# SmartThermo2_2.net
KiCad netlist of a schematic drawn in EAGLE
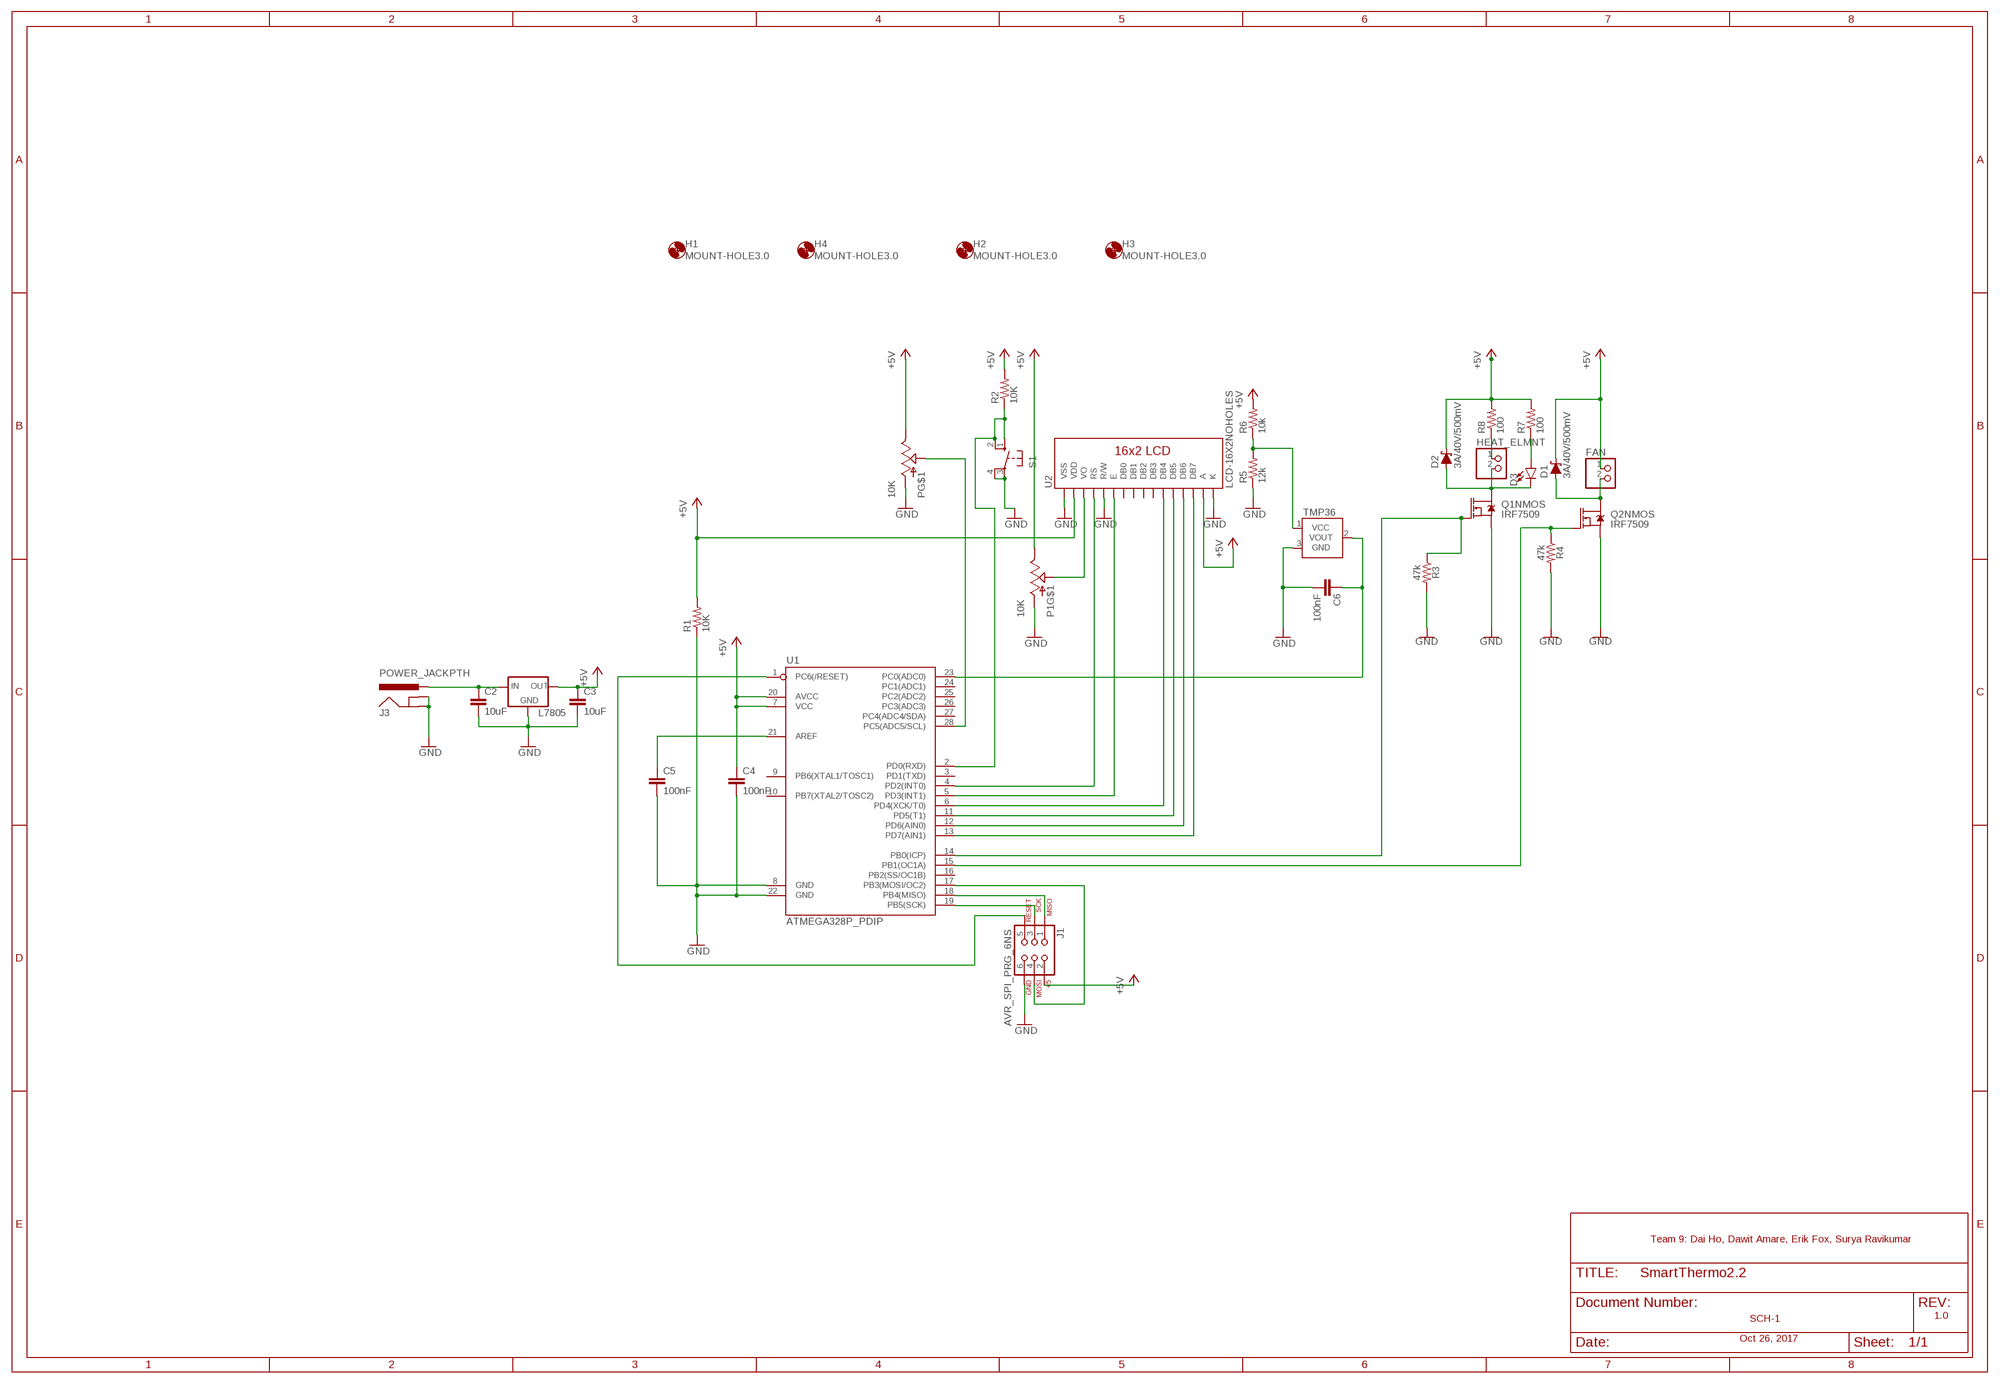
[diagram p0: schematic, sheet 1]

(export (version "E")
  (design (tool "Eeschema 10.0.6"))
  (components
    (comp (ref "C2")
      (value "10uF")
      (footprint "eagle-import:C7.5B3")
      (libsource (lib "eagle-import") (part "C7.5/3"))
    )
    (comp (ref "C3")
      (value "10uF")
      (footprint "eagle-import:C7.5B3")
      (libsource (lib "eagle-import") (part "C7.5/3"))
    )
    (comp (ref "C4")
      (value "100nF")
      (footprint "eagle-import:C2.5-2")
      (libsource (lib "eagle-import") (part "C2.5/2"))
    )
    (comp (ref "C5")
      (value "100nF")
      (footprint "eagle-import:C2.5-2")
      (libsource (lib "eagle-import") (part "C2.5/2"))
    )
    (comp (ref "C6")
      (value "100nF")
      (footprint "eagle-import:C2.5-2")
      (libsource (lib "eagle-import") (part "C2.5/2"))
    )
    (comp (ref "D1")
      (value "3A/40V/500mV")
      (footprint "eagle-import:SMA-DIODE")
      (libsource (lib "eagle-import") (part "DIODE-SCHOTTKY-B340A"))
    )
    (comp (ref "D2")
      (value "3A/40V/500mV")
      (footprint "eagle-import:SMA-DIODE")
      (libsource (lib "eagle-import") (part "DIODE-SCHOTTKY-B340A"))
    )
    (comp (ref "D3")
      (value "LED3MM")
      (footprint "eagle-import:LED_3MM")
      (libsource (lib "eagle-import") (part "LED3MM"))
    )
    (comp (ref "FAN")
      (value "PINHD-1X2/90")
      (footprint "eagle-import:1X02_90")
      (libsource (lib "eagle-import") (part "PINHD-1X2/90"))
    )
    (comp (ref "H1")
      (value "MOUNT-HOLE3.0")
      (footprint "eagle-import:3,0")
      (libsource (lib "eagle-import") (part "MOUNT-HOLE3.0"))
    )
    (comp (ref "H2")
      (value "MOUNT-HOLE3.0")
      (footprint "eagle-import:3,0")
      (libsource (lib "eagle-import") (part "MOUNT-HOLE3.0"))
    )
    (comp (ref "H3")
      (value "MOUNT-HOLE3.0")
      (footprint "eagle-import:3,0")
      (libsource (lib "eagle-import") (part "MOUNT-HOLE3.0"))
    )
    (comp (ref "H4")
      (value "MOUNT-HOLE3.0")
      (footprint "eagle-import:3,0")
      (libsource (lib "eagle-import") (part "MOUNT-HOLE3.0"))
    )
    (comp (ref "HEAT_ELMNT")
      (value "PINHD-1X2/90")
      (footprint "eagle-import:1X02_90")
      (libsource (lib "eagle-import") (part "PINHD-1X2/90"))
    )
    (comp (ref "J1")
      (value "AVR_SPI_PRG_6NS")
      (footprint "eagle-import:2X3-NS")
      (libsource (lib "eagle-import") (part "AVR_SPI_PRG_6NS"))
    )
    (comp (ref "J3")
      (value "POWER_JACKPTH")
      (footprint "eagle-import:POWER_JACK_PTH")
      (libsource (lib "eagle-import") (part "POWER_JACKPTH"))
    )
    (comp (ref "L7805")
      (value "78XXL")
      (footprint "eagle-import:78XXL")
      (libsource (lib "eagle-import") (part "78XXL"))
    )
    (comp (ref "P")
      (value "10K")
      (footprint "eagle-import:POT_PTH")
      (libsource (lib "eagle-import") (part "POT_SWITCHPOT_PTH"))
    )
    (comp (ref "P1")
      (value "10K")
      (footprint "eagle-import:POT_PTH")
      (libsource (lib "eagle-import") (part "POT_SWITCHPOT_PTH"))
    )
    (comp (ref "Q1")
      (value "IRF7509")
      (footprint "eagle-import:MSOP8")
      (libsource (lib "eagle-import") (part "IRF7509"))
    )
    (comp (ref "Q2")
      (value "IRF7509")
      (footprint "eagle-import:MSOP8")
      (libsource (lib "eagle-import") (part "IRF7509"))
    )
    (comp (ref "R1")
      (value "10K")
      (footprint "eagle-import:1206")
      (libsource (lib "eagle-import") (part "RESISTOR1206"))
    )
    (comp (ref "R2")
      (value "10K")
      (footprint "eagle-import:1206")
      (libsource (lib "eagle-import") (part "RESISTOR1206"))
    )
    (comp (ref "R3")
      (value "47k")
      (footprint "eagle-import:0603")
      (libsource (lib "eagle-import") (part "47KOHM-0603-1/10W-1%"))
    )
    (comp (ref "R4")
      (value "47k")
      (footprint "eagle-import:0603")
      (libsource (lib "eagle-import") (part "47KOHM-0603-1/10W-1%"))
    )
    (comp (ref "R5")
      (value "12k")
      (footprint "eagle-import:0204_5")
      (libsource (lib "eagle-import") (part "R-US_0204/5"))
    )
    (comp (ref "R6")
      (value "10k")
      (footprint "eagle-import:0204_5")
      (libsource (lib "eagle-import") (part "R-US_0204/5"))
    )
    (comp (ref "R7")
      (value "100")
      (footprint "eagle-import:0204_5")
      (libsource (lib "eagle-import") (part "R-US_0204/5"))
    )
    (comp (ref "R8")
      (value "100")
      (footprint "eagle-import:0204_5")
      (libsource (lib "eagle-import") (part "R-US_0204/5"))
    )
    (comp (ref "S1")
      (value "10-XX")
      (footprint "eagle-import:B3F-10XX")
      (fields (field (name "MPN") "B3F-1000"))
      (libsource (lib "eagle-import") (part "10-XX"))
    )
    (comp (ref "TMP36")
      (value "TMP36GT9")
      (footprint "eagle-import:TO-92")
      (libsource (lib "eagle-import") (part "TMP36GT9"))
    )
    (comp (ref "U1")
      (value "ATMEGA328P_PDIP")
      (footprint "eagle-import:DIL28-3")
      (libsource (lib "eagle-import") (part "ATMEGA328P_PDIP"))
    )
    (comp (ref "U2")
      (value "LCD-16X2NOHOLES")
      (footprint "eagle-import:LCD-16X2_NOHOLES")
      (libsource (lib "eagle-import") (part "LCD-16X2NOHOLES"))
    )
  )
  (nets
    (net (code "1") (name "+5V") (class "Default")
      (node (ref "C3") (pin "1") (pinfunction "1_1") (pintype "passive"))
      (node (ref "C4") (pin "1") (pinfunction "1_1") (pintype "passive"))
      (node (ref "D1") (pin "C") (pinfunction "C_C") (pintype "passive"))
      (node (ref "D2") (pin "C") (pinfunction "C_C") (pintype "passive"))
      (node (ref "FAN") (pin "1") (pinfunction "1_1") (pintype "passive"))
      (node (ref "J1") (pin "2") (pinfunction "2_2") (pintype "passive"))
      (node (ref "L7805") (pin "OUT") (pinfunction "OUT_OUT") (pintype "passive"))
      (node (ref "P") (pin "E@2") (pinfunction "E_E@2") (pintype "passive"))
      (node (ref "P1") (pin "E@2") (pinfunction "E_E@2") (pintype "passive"))
      (node (ref "R1") (pin "2") (pinfunction "2_2") (pintype "passive"))
      (node (ref "R2") (pin "2") (pinfunction "2_2") (pintype "passive"))
      (node (ref "R6") (pin "2") (pinfunction "2_2") (pintype "passive"))
      (node (ref "R7") (pin "2") (pinfunction "2_2") (pintype "passive"))
      (node (ref "R8") (pin "2") (pinfunction "2_2") (pintype "passive"))
      (node (ref "U1") (pin "20") (pinfunction "AVCC_20") (pintype "bidirectional"))
      (node (ref "U1") (pin "7") (pinfunction "VCC_7") (pintype "bidirectional"))
      (node (ref "U2") (pin "15") (pinfunction "A_15") (pintype "power_in"))
      (node (ref "U2") (pin "2") (pinfunction "VDD_2") (pintype "power_in"))
    )
    (net (code "2") (name "GND") (class "Default")
      (node (ref "C2") (pin "2") (pinfunction "2_2") (pintype "passive"))
      (node (ref "C3") (pin "2") (pinfunction "2_2") (pintype "passive"))
      (node (ref "C4") (pin "2") (pinfunction "2_2") (pintype "passive"))
      (node (ref "C5") (pin "2") (pinfunction "2_2") (pintype "passive"))
      (node (ref "C6") (pin "2") (pinfunction "2_2") (pintype "passive"))
      (node (ref "J1") (pin "6") (pinfunction "6_6") (pintype "passive"))
      (node (ref "J3") (pin "GND") (pinfunction "GND_GND") (pintype "bidirectional"))
      (node (ref "J3") (pin "GNDBREAK") (pinfunction "GNDBREAK_GNDBREAK") (pintype "bidirectional"))
      (node (ref "L7805") (pin "GND") (pinfunction "GND_GND") (pintype "input"))
      (node (ref "P") (pin "E@1") (pinfunction "A_E@1") (pintype "passive"))
      (node (ref "P1") (pin "E@1") (pinfunction "A_E@1") (pintype "passive"))
      (node (ref "Q1") (pin "1") (pinfunction "S_1") (pintype "bidirectional"))
      (node (ref "Q2") (pin "1") (pinfunction "S_1") (pintype "bidirectional"))
      (node (ref "R1") (pin "1") (pinfunction "1_1") (pintype "passive"))
      (node (ref "R3") (pin "2") (pinfunction "2_2") (pintype "passive"))
      (node (ref "R4") (pin "2") (pinfunction "2_2") (pintype "passive"))
      (node (ref "R5") (pin "1") (pinfunction "1_1") (pintype "passive"))
      (node (ref "S1") (pin "3") (pinfunction "P_3") (pintype "passive"))
      (node (ref "S1") (pin "4") (pinfunction "P1_4") (pintype "passive"))
      (node (ref "TMP36") (pin "3") (pinfunction "GND_3") (pintype "bidirectional"))
      (node (ref "U1") (pin "22") (pinfunction "GND_22") (pintype "bidirectional"))
      (node (ref "U1") (pin "8") (pinfunction "GND_8") (pintype "bidirectional"))
      (node (ref "U2") (pin "1") (pinfunction "VSS_1") (pintype "power_in"))
      (node (ref "U2") (pin "16") (pinfunction "K_16") (pintype "power_in"))
      (node (ref "U2") (pin "5") (pinfunction "R/W_5") (pintype "input"))
    )
    (net (code "3") (name "Net-(C2-Pad1)") (class "Default")
      (node (ref "C2") (pin "1") (pinfunction "1_1") (pintype "passive"))
      (node (ref "J3") (pin "PWR") (pinfunction "PWR_PWR") (pintype "bidirectional"))
      (node (ref "L7805") (pin "IN") (pinfunction "IN_IN") (pintype "input"))
    )
    (net (code "4") (name "Net-(D1-PadA)") (class "Default")
      (node (ref "D1") (pin "A") (pinfunction "A_A") (pintype "passive"))
      (node (ref "FAN") (pin "2") (pinfunction "2_2") (pintype "passive"))
      (node (ref "Q2") (pin "7") (pinfunction "D_7") (pintype "bidirectional"))
      (node (ref "Q2") (pin "8") (pinfunction "D_8") (pintype "bidirectional"))
    )
    (net (code "5") (name "Net-(D3-C)") (class "Default")
      (node (ref "D2") (pin "A") (pinfunction "A_A") (pintype "passive"))
      (node (ref "D3") (pin "K") (pinfunction "C_K") (pintype "passive"))
      (node (ref "HEAT_ELMNT") (pin "2") (pinfunction "2_2") (pintype "passive"))
      (node (ref "Q1") (pin "7") (pinfunction "D_7") (pintype "bidirectional"))
      (node (ref "Q1") (pin "8") (pinfunction "D_8") (pintype "bidirectional"))
    )
    (net (code "6") (name "Net-(D3-PadA)") (class "Default")
      (node (ref "D3") (pin "A") (pinfunction "A_A") (pintype "passive"))
      (node (ref "R7") (pin "1") (pinfunction "1_1") (pintype "passive"))
    )
    (net (code "7") (name "Net-(HEAT_ELMNT-Pad1)") (class "Default")
      (node (ref "HEAT_ELMNT") (pin "1") (pinfunction "1_1") (pintype "passive"))
      (node (ref "R8") (pin "1") (pinfunction "1_1") (pintype "passive"))
    )
    (net (code "8") (name "Net-(P1A-S)") (class "Default")
      (node (ref "P1") (pin "WAND") (pinfunction "S_WAND") (pintype "passive"))
      (node (ref "U2") (pin "3") (pinfunction "VO_3") (pintype "bidirectional"))
    )
    (net (code "9") (name "Net-(PA-S)") (class "Default")
      (node (ref "P") (pin "WAND") (pinfunction "S_WAND") (pintype "passive"))
      (node (ref "U1") (pin "28") (pinfunction "PC5(ADC5/SCL)_28") (pintype "bidirectional"))
    )
    (net (code "10") (name "Net-(Q1A-G)") (class "Default")
      (node (ref "Q1") (pin "2") (pinfunction "G_2") (pintype "bidirectional"))
      (node (ref "R3") (pin "1") (pinfunction "1_1") (pintype "passive"))
      (node (ref "U1") (pin "14") (pinfunction "PB0(ICP)_14") (pintype "bidirectional"))
    )
    (net (code "11") (name "Net-(Q2A-G)") (class "Default")
      (node (ref "Q2") (pin "2") (pinfunction "G_2") (pintype "bidirectional"))
      (node (ref "R4") (pin "1") (pinfunction "1_1") (pintype "passive"))
      (node (ref "U1") (pin "15") (pinfunction "PB1(OC1A)_15") (pintype "bidirectional"))
    )
    (net (code "12") (name "Net-(S1-S)") (class "Default")
      (node (ref "R2") (pin "1") (pinfunction "1_1") (pintype "passive"))
      (node (ref "S1") (pin "1") (pinfunction "S_1") (pintype "passive"))
      (node (ref "S1") (pin "2") (pinfunction "S1_2") (pintype "passive"))
      (node (ref "U1") (pin "2") (pinfunction "PD0(RXD)_2") (pintype "bidirectional"))
    )
    (net (code "13") (name "Net-(TMP36-VCC)") (class "Default")
      (node (ref "R5") (pin "2") (pinfunction "2_2") (pintype "passive"))
      (node (ref "R6") (pin "1") (pinfunction "1_1") (pintype "passive"))
      (node (ref "TMP36") (pin "1") (pinfunction "VCC_1") (pintype "bidirectional"))
    )
    (net (code "14") (name "Net-(TMP36-VOUT)") (class "Default")
      (node (ref "C6") (pin "1") (pinfunction "1_1") (pintype "passive"))
      (node (ref "TMP36") (pin "2") (pinfunction "VOUT_2") (pintype "bidirectional"))
      (node (ref "U1") (pin "23") (pinfunction "PC0(ADC0)_23") (pintype "bidirectional"))
    )
    (net (code "15") (name "Net-(U1-AREF)") (class "Default")
      (node (ref "C5") (pin "1") (pinfunction "1_1") (pintype "passive"))
      (node (ref "U1") (pin "21") (pinfunction "AREF_21") (pintype "bidirectional"))
    )
    (net (code "16") (name "Net-(U1-PB3(MOSI{slash}OC2))") (class "Default")
      (node (ref "J1") (pin "4") (pinfunction "4_4") (pintype "passive"))
      (node (ref "U1") (pin "17") (pinfunction "PB3(MOSI/OC2)_17") (pintype "bidirectional"))
    )
    (net (code "17") (name "Net-(U1-PB4(MISO))") (class "Default")
      (node (ref "J1") (pin "1") (pinfunction "1_1") (pintype "passive"))
      (node (ref "U1") (pin "18") (pinfunction "PB4(MISO)_18") (pintype "bidirectional"))
    )
    (net (code "18") (name "Net-(U1-PB5(SCK))") (class "Default")
      (node (ref "J1") (pin "3") (pinfunction "3_3") (pintype "passive"))
      (node (ref "U1") (pin "19") (pinfunction "PB5(SCK)_19") (pintype "bidirectional"))
    )
    (net (code "19") (name "Net-(U1-PC6({slash}RESET))") (class "Default")
      (node (ref "J1") (pin "5") (pinfunction "5_5") (pintype "passive"))
      (node (ref "U1") (pin "1") (pinfunction "PC6(/RESET)_1") (pintype "bidirectional"))
    )
    (net (code "20") (name "Net-(U1-PD2(INT0))") (class "Default")
      (node (ref "U1") (pin "4") (pinfunction "PD2(INT0)_4") (pintype "bidirectional"))
      (node (ref "U2") (pin "4") (pinfunction "RS_4") (pintype "input"))
    )
    (net (code "21") (name "Net-(U1-PD3(INT1))") (class "Default")
      (node (ref "U1") (pin "5") (pinfunction "PD3(INT1)_5") (pintype "bidirectional"))
      (node (ref "U2") (pin "6") (pinfunction "E_6") (pintype "input"))
    )
    (net (code "22") (name "Net-(U1-PD4(XCK{slash}T0))") (class "Default")
      (node (ref "U1") (pin "6") (pinfunction "PD4(XCK/T0)_6") (pintype "bidirectional"))
      (node (ref "U2") (pin "11") (pinfunction "DB4_11") (pintype "bidirectional"))
    )
    (net (code "23") (name "Net-(U1-PD5(T1))") (class "Default")
      (node (ref "U1") (pin "11") (pinfunction "PD5(T1)_11") (pintype "bidirectional"))
      (node (ref "U2") (pin "12") (pinfunction "DB5_12") (pintype "bidirectional"))
    )
    (net (code "24") (name "Net-(U1-PD6(AIN0))") (class "Default")
      (node (ref "U1") (pin "12") (pinfunction "PD6(AIN0)_12") (pintype "bidirectional"))
      (node (ref "U2") (pin "13") (pinfunction "DB6_13") (pintype "bidirectional"))
    )
    (net (code "25") (name "Net-(U1-PD7(AIN1))") (class "Default")
      (node (ref "U1") (pin "13") (pinfunction "PD7(AIN1)_13") (pintype "bidirectional"))
      (node (ref "U2") (pin "14") (pinfunction "DB7_14") (pintype "bidirectional"))
    )
    (net (code "26") (name "unconnected-(U1-PB2(SS{slash}OC1B)-Pad16)") (class "Default")
      (node (ref "U1") (pin "16") (pinfunction "PB2(SS/OC1B)_16") (pintype "bidirectional"))
    )
    (net (code "27") (name "unconnected-(U1-PB6(XTAL1{slash}TOSC1)-Pad9)") (class "Default")
      (node (ref "U1") (pin "9") (pinfunction "PB6(XTAL1/TOSC1)_9") (pintype "bidirectional"))
    )
    (net (code "28") (name "unconnected-(U1-PB7(XTAL2{slash}TOSC2)-Pad10)") (class "Default")
      (node (ref "U1") (pin "10") (pinfunction "PB7(XTAL2/TOSC2)_10") (pintype "bidirectional"))
    )
    (net (code "29") (name "unconnected-(U1-PC1(ADC1)-Pad24)") (class "Default")
      (node (ref "U1") (pin "24") (pinfunction "PC1(ADC1)_24") (pintype "bidirectional"))
    )
    (net (code "30") (name "unconnected-(U1-PC2(ADC2)-Pad25)") (class "Default")
      (node (ref "U1") (pin "25") (pinfunction "PC2(ADC2)_25") (pintype "bidirectional"))
    )
    (net (code "31") (name "unconnected-(U1-PC3(ADC3)-Pad26)") (class "Default")
      (node (ref "U1") (pin "26") (pinfunction "PC3(ADC3)_26") (pintype "bidirectional"))
    )
    (net (code "32") (name "unconnected-(U1-PC4(ADC4{slash}SDA)-Pad27)") (class "Default")
      (node (ref "U1") (pin "27") (pinfunction "PC4(ADC4/SDA)_27") (pintype "bidirectional"))
    )
    (net (code "33") (name "unconnected-(U1-PD1(TXD)-Pad3)") (class "Default")
      (node (ref "U1") (pin "3") (pinfunction "PD1(TXD)_3") (pintype "bidirectional"))
    )
    (net (code "34") (name "unconnected-(U2-DB0-Pad7)") (class "Default")
      (node (ref "U2") (pin "7") (pinfunction "DB0_7") (pintype "bidirectional"))
    )
    (net (code "35") (name "unconnected-(U2-DB1-Pad8)") (class "Default")
      (node (ref "U2") (pin "8") (pinfunction "DB1_8") (pintype "bidirectional"))
    )
    (net (code "36") (name "unconnected-(U2-DB2-Pad9)") (class "Default")
      (node (ref "U2") (pin "9") (pinfunction "DB2_9") (pintype "bidirectional"))
    )
    (net (code "37") (name "unconnected-(U2-DB3-Pad10)") (class "Default")
      (node (ref "U2") (pin "10") (pinfunction "DB3_10") (pintype "bidirectional"))
    )
  )
)
